# LineIn.net
KiCad netlist of a schematic drawn in EAGLE
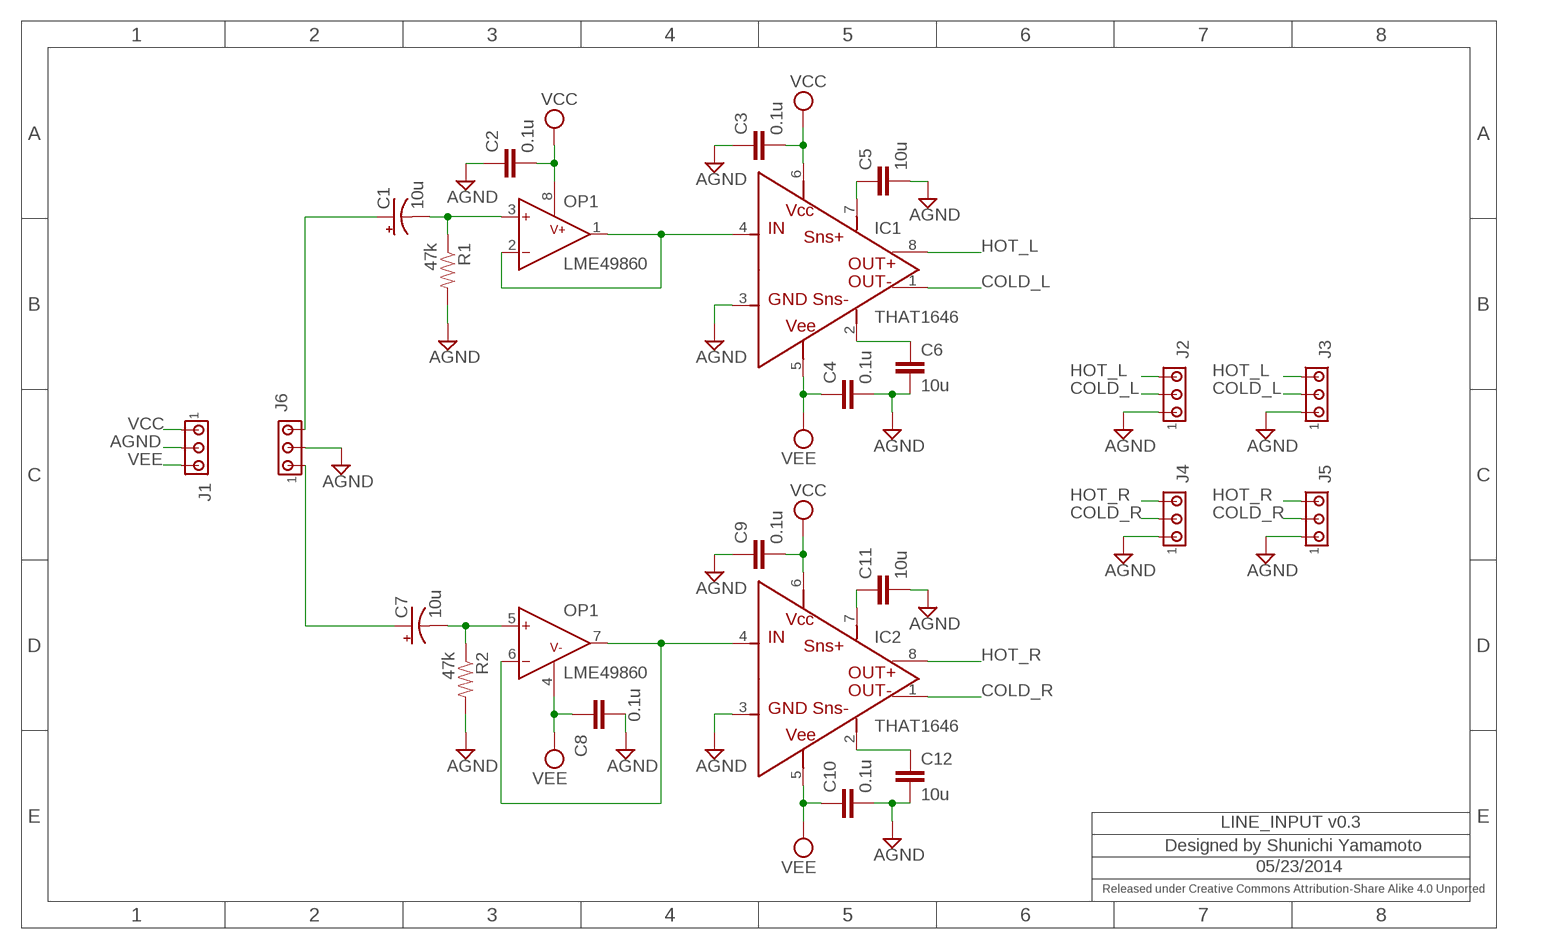
[diagram p0: schematic, sheet 1]

(export (version "E")
  (design (tool "Eeschema 10.0.6"))
  (components
    (comp (ref "C1")
      (value "10u")
      (footprint "eagle-import:UD-5X5,8_NICHICON")
      (libsource (lib "eagle-import") (part "CPOL-USUD-5X5,8"))
    )
    (comp (ref "C2")
      (value "0.1u")
      (footprint "eagle-import:C2012")
      (libsource (lib "eagle-import") (part "C-EUC2012"))
    )
    (comp (ref "C3")
      (value "0.1u")
      (footprint "eagle-import:C2012")
      (libsource (lib "eagle-import") (part "C-EUC2012"))
    )
    (comp (ref "C4")
      (value "0.1u")
      (footprint "eagle-import:C2012")
      (libsource (lib "eagle-import") (part "C-EUC2012"))
    )
    (comp (ref "C5")
      (value "10u")
      (footprint "eagle-import:C2012")
      (libsource (lib "eagle-import") (part "C-EUC2012"))
    )
    (comp (ref "C6")
      (value "10u")
      (footprint "eagle-import:C2012")
      (libsource (lib "eagle-import") (part "C-EUC2012"))
    )
    (comp (ref "C7")
      (value "10u")
      (footprint "eagle-import:UD-5X5,8_NICHICON")
      (libsource (lib "eagle-import") (part "CPOL-USUD-5X5,8"))
    )
    (comp (ref "C8")
      (value "0.1u")
      (footprint "eagle-import:C2012")
      (libsource (lib "eagle-import") (part "C-EUC2012"))
    )
    (comp (ref "C9")
      (value "0.1u")
      (footprint "eagle-import:C2012")
      (libsource (lib "eagle-import") (part "C-EUC2012"))
    )
    (comp (ref "C10")
      (value "0.1u")
      (footprint "eagle-import:C2012")
      (libsource (lib "eagle-import") (part "C-EUC2012"))
    )
    (comp (ref "C11")
      (value "10u")
      (footprint "eagle-import:C2012")
      (libsource (lib "eagle-import") (part "C-EUC2012"))
    )
    (comp (ref "C12")
      (value "10u")
      (footprint "eagle-import:C2012")
      (libsource (lib "eagle-import") (part "C-EUC2012"))
    )
    (comp (ref "IC1")
      (value "THAT1646")
      (footprint "eagle-import:SOIC8")
      (libsource (lib "eagle-import") (part "THAT1646"))
    )
    (comp (ref "IC2")
      (value "THAT1646")
      (footprint "eagle-import:SOIC8")
      (libsource (lib "eagle-import") (part "THAT1646"))
    )
    (comp (ref "J1")
      (value "MTA03-156")
      (footprint "eagle-import:1X3MTA")
      (libsource (lib "eagle-import") (part "MTA03-156"))
    )
    (comp (ref "J2")
      (value "MTA03-100")
      (footprint "eagle-import:10X03MTA")
      (libsource (lib "eagle-import") (part "MTA03-100"))
    )
    (comp (ref "J3")
      (value "MTA03-100")
      (footprint "eagle-import:10X03MTA")
      (libsource (lib "eagle-import") (part "MTA03-100"))
    )
    (comp (ref "J4")
      (value "MTA03-100")
      (footprint "eagle-import:10X03MTA")
      (libsource (lib "eagle-import") (part "MTA03-100"))
    )
    (comp (ref "J5")
      (value "MTA03-100")
      (footprint "eagle-import:10X03MTA")
      (libsource (lib "eagle-import") (part "MTA03-100"))
    )
    (comp (ref "J6")
      (value "MTA03-100")
      (footprint "eagle-import:10X03MTA")
      (libsource (lib "eagle-import") (part "MTA03-100"))
    )
    (comp (ref "OP1")
      (value "LME49860")
      (footprint "eagle-import:SOIC8@1")
      (libsource (lib "eagle-import") (part "LME49860"))
    )
    (comp (ref "R1")
      (value "47k")
      (footprint "eagle-import:0805")
      (libsource (lib "eagle-import") (part "RESISTOR0805-RES"))
    )
    (comp (ref "R2")
      (value "47k")
      (footprint "eagle-import:0805")
      (libsource (lib "eagle-import") (part "RESISTOR0805-RES"))
    )
  )
  (nets
    (net (code "1") (name "/COLD_L") (class "Default")
      (node (ref "IC1") (pin "1") (pinfunction "OUT-_1") (pintype "output"))
      (node (ref "J2") (pin "2") (pinfunction "2_2") (pintype "passive"))
      (node (ref "J3") (pin "2") (pinfunction "2_2") (pintype "passive"))
    )
    (net (code "2") (name "/COLD_R") (class "Default")
      (node (ref "IC2") (pin "1") (pinfunction "OUT-_1") (pintype "output"))
      (node (ref "J4") (pin "2") (pinfunction "2_2") (pintype "passive"))
      (node (ref "J5") (pin "2") (pinfunction "2_2") (pintype "passive"))
    )
    (net (code "3") (name "/HOT_L") (class "Default")
      (node (ref "IC1") (pin "8") (pinfunction "OUT+_8") (pintype "output"))
      (node (ref "J2") (pin "3") (pinfunction "3_3") (pintype "passive"))
      (node (ref "J3") (pin "3") (pinfunction "3_3") (pintype "passive"))
    )
    (net (code "4") (name "/HOT_R") (class "Default")
      (node (ref "IC2") (pin "8") (pinfunction "OUT+_8") (pintype "output"))
      (node (ref "J4") (pin "3") (pinfunction "3_3") (pintype "passive"))
      (node (ref "J5") (pin "3") (pinfunction "3_3") (pintype "passive"))
    )
    (net (code "5") (name "AGND") (class "Default")
      (node (ref "C10") (pin "2") (pinfunction "2_2") (pintype "passive"))
      (node (ref "C11") (pin "2") (pinfunction "2_2") (pintype "passive"))
      (node (ref "C12") (pin "2") (pinfunction "2_2") (pintype "passive"))
      (node (ref "C2") (pin "1") (pinfunction "1_1") (pintype "passive"))
      (node (ref "C3") (pin "1") (pinfunction "1_1") (pintype "passive"))
      (node (ref "C4") (pin "2") (pinfunction "2_2") (pintype "passive"))
      (node (ref "C5") (pin "2") (pinfunction "2_2") (pintype "passive"))
      (node (ref "C6") (pin "2") (pinfunction "2_2") (pintype "passive"))
      (node (ref "C8") (pin "2") (pinfunction "2_2") (pintype "passive"))
      (node (ref "C9") (pin "1") (pinfunction "1_1") (pintype "passive"))
      (node (ref "IC1") (pin "3") (pinfunction "GND_3") (pintype "input"))
      (node (ref "IC2") (pin "3") (pinfunction "GND_3") (pintype "input"))
      (node (ref "J1") (pin "2") (pinfunction "2_2") (pintype "passive"))
      (node (ref "J2") (pin "1") (pinfunction "1_1") (pintype "passive"))
      (node (ref "J3") (pin "1") (pinfunction "1_1") (pintype "passive"))
      (node (ref "J4") (pin "1") (pinfunction "1_1") (pintype "passive"))
      (node (ref "J5") (pin "1") (pinfunction "1_1") (pintype "passive"))
      (node (ref "J6") (pin "2") (pinfunction "2_2") (pintype "passive"))
      (node (ref "R1") (pin "2") (pinfunction "2_2") (pintype "passive"))
      (node (ref "R2") (pin "2") (pinfunction "2_2") (pintype "passive"))
    )
    (net (code "6") (name "Net-(C1-Pad+)") (class "Default")
      (node (ref "C1") (pin "+") (pinfunction "+_+") (pintype "passive"))
      (node (ref "J6") (pin "3") (pinfunction "3_3") (pintype "passive"))
    )
    (net (code "7") (name "Net-(C7-Pad+)") (class "Default")
      (node (ref "C7") (pin "+") (pinfunction "+_+") (pintype "passive"))
      (node (ref "J6") (pin "1") (pinfunction "1_1") (pintype "passive"))
    )
    (net (code "8") (name "Net-(IC1-IN)") (class "Default")
      (node (ref "IC1") (pin "4") (pinfunction "IN_4") (pintype "input"))
      (node (ref "OP1") (pin "1") (pinfunction "OUTA_1") (pintype "output"))
      (node (ref "OP1") (pin "2") (pinfunction "INA-_2") (pintype "input"))
    )
    (net (code "9") (name "Net-(IC1-SNS+)") (class "Default")
      (node (ref "C5") (pin "1") (pinfunction "1_1") (pintype "passive"))
      (node (ref "IC1") (pin "7") (pinfunction "SNS+_7") (pintype "power_in"))
    )
    (net (code "10") (name "Net-(IC1-SNS-)") (class "Default")
      (node (ref "C6") (pin "1") (pinfunction "1_1") (pintype "passive"))
      (node (ref "IC1") (pin "2") (pinfunction "SNS-_2") (pintype "input"))
    )
    (net (code "11") (name "Net-(IC2-IN)") (class "Default")
      (node (ref "IC2") (pin "4") (pinfunction "IN_4") (pintype "input"))
      (node (ref "OP1") (pin "6") (pinfunction "INB-_6") (pintype "input"))
      (node (ref "OP1") (pin "7") (pinfunction "OUTB_7") (pintype "output"))
    )
    (net (code "12") (name "Net-(IC2-SNS+)") (class "Default")
      (node (ref "C11") (pin "1") (pinfunction "1_1") (pintype "passive"))
      (node (ref "IC2") (pin "7") (pinfunction "SNS+_7") (pintype "power_in"))
    )
    (net (code "13") (name "Net-(IC2-SNS-)") (class "Default")
      (node (ref "C12") (pin "1") (pinfunction "1_1") (pintype "passive"))
      (node (ref "IC2") (pin "2") (pinfunction "SNS-_2") (pintype "input"))
    )
    (net (code "14") (name "Net-(OP1A-INA+)") (class "Default")
      (node (ref "C1") (pin "-") (pinfunction "-_-") (pintype "passive"))
      (node (ref "OP1") (pin "3") (pinfunction "INA+_3") (pintype "input"))
      (node (ref "R1") (pin "1") (pinfunction "1_1") (pintype "passive"))
    )
    (net (code "15") (name "Net-(OP1B-INB+)") (class "Default")
      (node (ref "C7") (pin "-") (pinfunction "-_-") (pintype "passive"))
      (node (ref "OP1") (pin "5") (pinfunction "INB+_5") (pintype "input"))
      (node (ref "R2") (pin "1") (pinfunction "1_1") (pintype "passive"))
    )
    (net (code "16") (name "VCC") (class "Default")
      (node (ref "C2") (pin "2") (pinfunction "2_2") (pintype "passive"))
      (node (ref "C3") (pin "2") (pinfunction "2_2") (pintype "passive"))
      (node (ref "C9") (pin "2") (pinfunction "2_2") (pintype "passive"))
      (node (ref "IC1") (pin "6") (pinfunction "VCC_6") (pintype "bidirectional"))
      (node (ref "IC2") (pin "6") (pinfunction "VCC_6") (pintype "bidirectional"))
      (node (ref "J1") (pin "1") (pinfunction "1_1") (pintype "passive"))
      (node (ref "OP1") (pin "8") (pinfunction "V+_8") (pintype "power_in"))
    )
    (net (code "17") (name "VEE") (class "Default")
      (node (ref "C10") (pin "1") (pinfunction "1_1") (pintype "passive"))
      (node (ref "C4") (pin "1") (pinfunction "1_1") (pintype "passive"))
      (node (ref "C8") (pin "1") (pinfunction "1_1") (pintype "passive"))
      (node (ref "IC1") (pin "5") (pinfunction "VEE_5") (pintype "input"))
      (node (ref "IC2") (pin "5") (pinfunction "VEE_5") (pintype "input"))
      (node (ref "J1") (pin "3") (pinfunction "3_3") (pintype "passive"))
      (node (ref "OP1") (pin "4") (pinfunction "V-_4") (pintype "power_in"))
    )
  )
)
